# DAPlink_STM32F103-v1_0_0.net
KiCad netlist of a schematic drawn in EAGLE
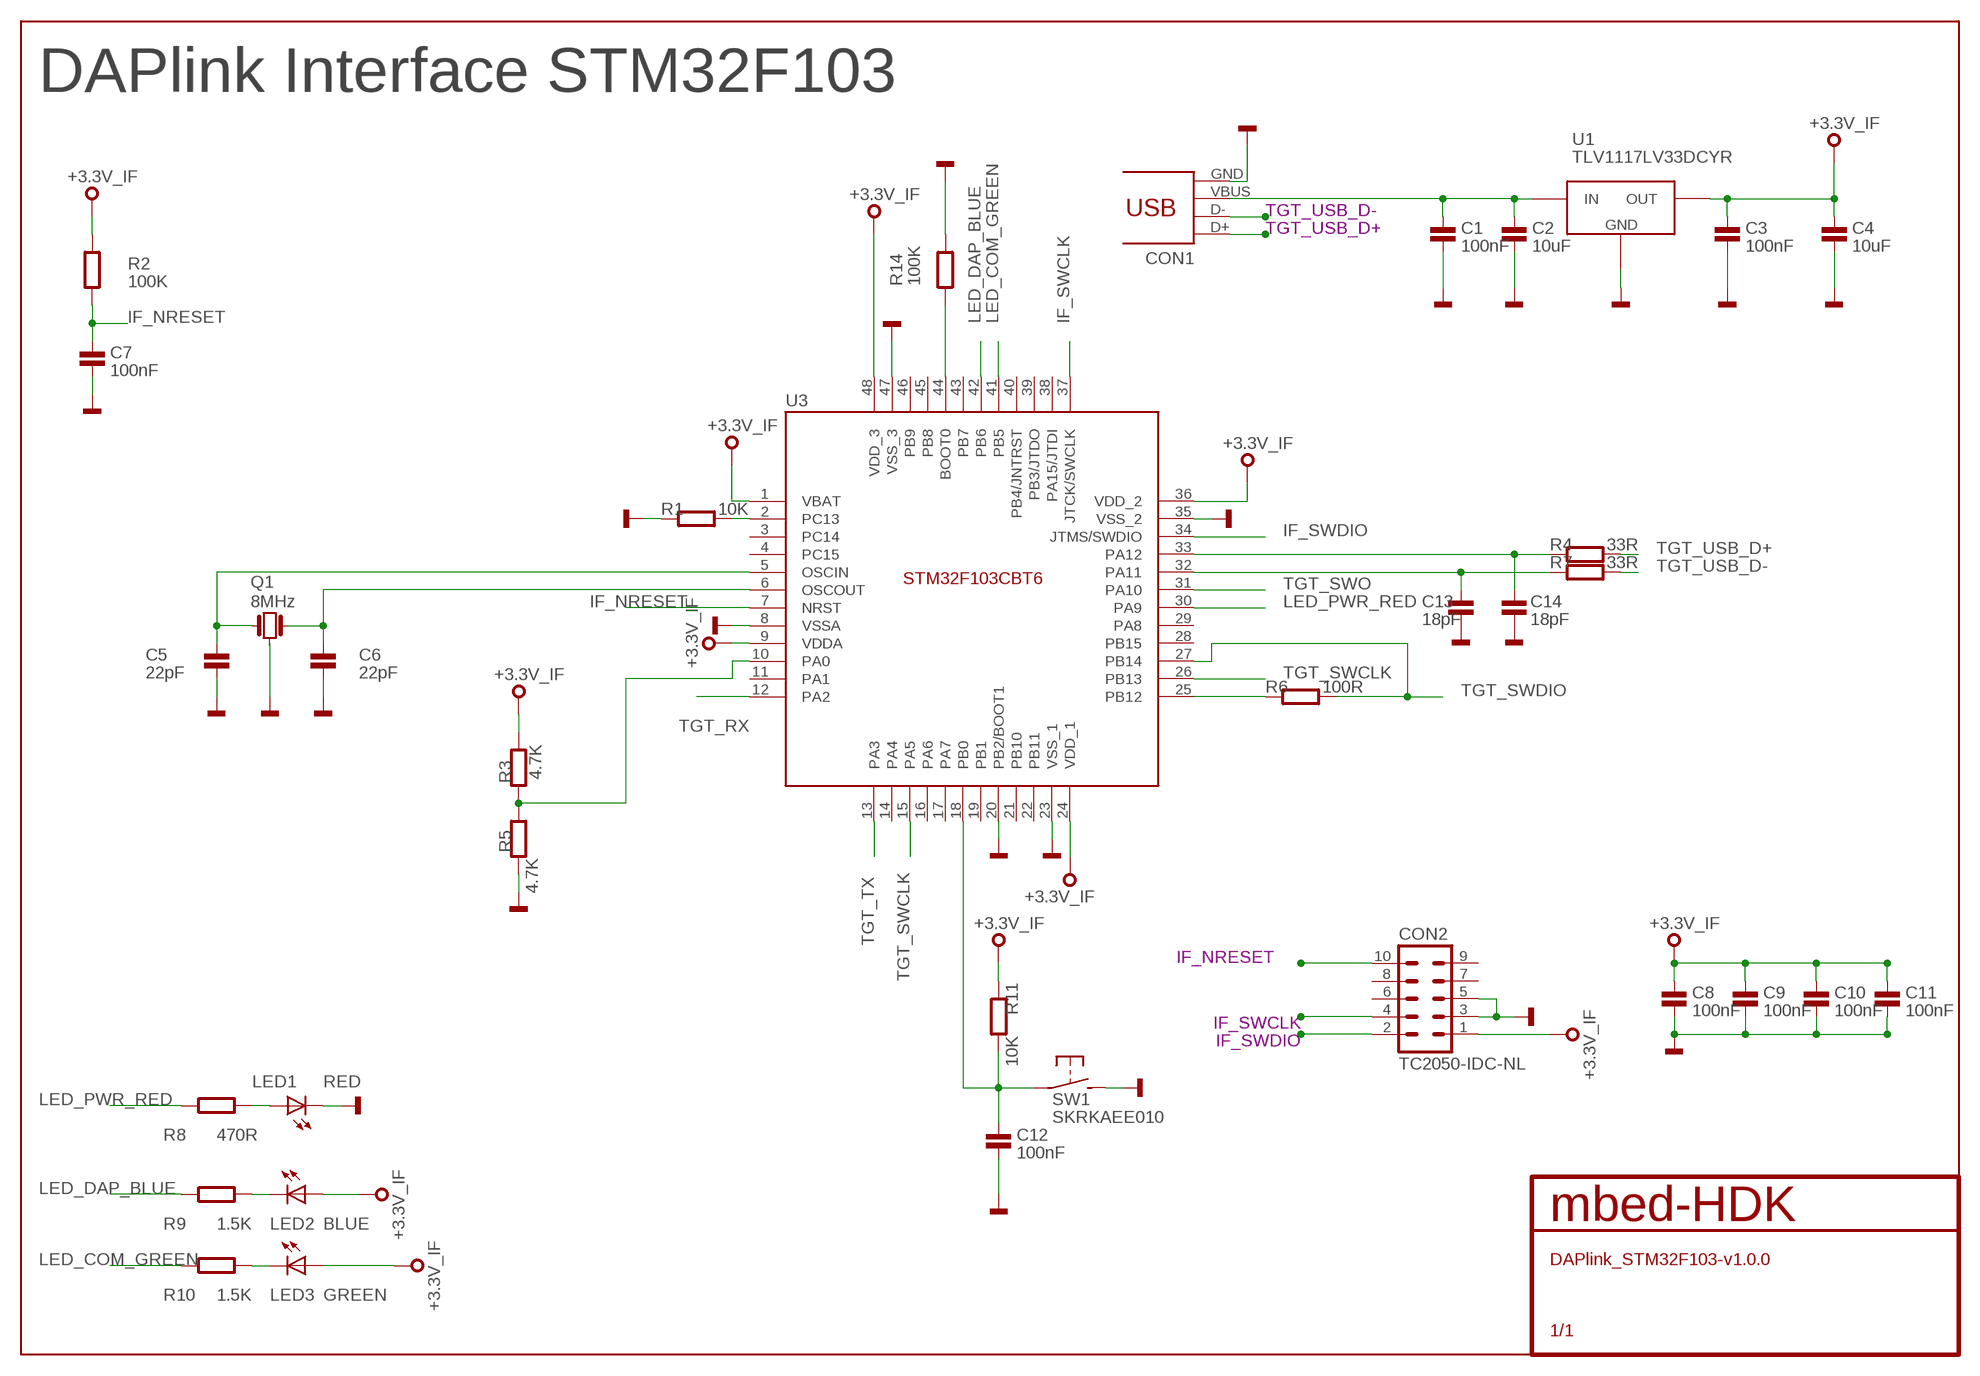
[diagram p0: schematic, sheet 1]

(export (version "E")
  (design (tool "Eeschema 10.0.6"))
  (components
    (comp (ref "C1")
      (value "100nF")
      (footprint "eagle-import:0402")
      (libsource (lib "eagle-import") (part "mbed-HDK-RLCQ_CAPACITOR0402"))
    )
    (comp (ref "C2")
      (value "10uF")
      (footprint "eagle-import:0603")
      (libsource (lib "eagle-import") (part "CAPACITOR0603"))
    )
    (comp (ref "C3")
      (value "100nF")
      (footprint "eagle-import:0402")
      (libsource (lib "eagle-import") (part "mbed-HDK-RLCQ_CAPACITOR0402"))
    )
    (comp (ref "C4")
      (value "10uF")
      (footprint "eagle-import:0603")
      (libsource (lib "eagle-import") (part "CAPACITOR0603"))
    )
    (comp (ref "C5")
      (value "22pF")
      (footprint "eagle-import:0402")
      (libsource (lib "eagle-import") (part "CAPACITOR0402"))
    )
    (comp (ref "C6")
      (value "22pF")
      (footprint "eagle-import:0402")
      (libsource (lib "eagle-import") (part "CAPACITOR0402"))
    )
    (comp (ref "C7")
      (value "100nF")
      (footprint "eagle-import:0402")
      (libsource (lib "eagle-import") (part "mbed-HDK-RLCQ_CAPACITOR0402"))
    )
    (comp (ref "C8")
      (value "100nF")
      (footprint "eagle-import:0402")
      (libsource (lib "eagle-import") (part "mbed-HDK-RLCQ_CAPACITOR0402"))
    )
    (comp (ref "C9")
      (value "100nF")
      (footprint "eagle-import:0402")
      (libsource (lib "eagle-import") (part "mbed-HDK-RLCQ_CAPACITOR0402"))
    )
    (comp (ref "C10")
      (value "100nF")
      (footprint "eagle-import:0402")
      (libsource (lib "eagle-import") (part "mbed-HDK-RLCQ_CAPACITOR0402"))
    )
    (comp (ref "C11")
      (value "100nF")
      (footprint "eagle-import:0402")
      (libsource (lib "eagle-import") (part "mbed-HDK-RLCQ_CAPACITOR0402"))
    )
    (comp (ref "C12")
      (value "100nF")
      (footprint "eagle-import:0402")
      (libsource (lib "eagle-import") (part "mbed-HDK-RLCQ_CAPACITOR0402"))
    )
    (comp (ref "C13")
      (value "18pF")
      (footprint "eagle-import:0402")
      (libsource (lib "eagle-import") (part "CAPACITOR0402"))
    )
    (comp (ref "C14")
      (value "18pF")
      (footprint "eagle-import:0402")
      (libsource (lib "eagle-import") (part "CAPACITOR0402"))
    )
    (comp (ref "CON1")
      (value "47346-0001")
      (footprint "eagle-import:USB-MICRO-B-H")
      (fields (field (name "MF") "MOLEX"))
      (libsource (lib "eagle-import") (part "47346-0001"))
    )
    (comp (ref "CON2")
      (value "TC2050-IDC-NL")
      (footprint "eagle-import:TC2050-IDC-NL")
      (libsource (lib "eagle-import") (part "TC2050-IDC-NL"))
    )
    (comp (ref "LED1")
      (value "RED")
      (footprint "eagle-import:CHIPLED_0603")
      (libsource (lib "eagle-import") (part "LED0603"))
    )
    (comp (ref "LED2")
      (value "BLUE")
      (footprint "eagle-import:CHIPLED_0603")
      (libsource (lib "eagle-import") (part "LED0603"))
    )
    (comp (ref "LED3")
      (value "GREEN")
      (footprint "eagle-import:CHIPLED_0603")
      (libsource (lib "eagle-import") (part "LED0603"))
    )
    (comp (ref "Q1")
      (value "8MHz")
      (footprint "eagle-import:CSTCE8M00G55-R0")
      (fields (field (name "MF") "Murata"))
      (libsource (lib "eagle-import") (part "CSTCE8M00G55-R0"))
    )
    (comp (ref "R1")
      (value "10K")
      (footprint "eagle-import:0402")
      (libsource (lib "eagle-import") (part "RESISTOR0402"))
    )
    (comp (ref "R2")
      (value "100K")
      (footprint "eagle-import:0402")
      (libsource (lib "eagle-import") (part "mbed-HDK-RLCQ_RESISTOR0402"))
    )
    (comp (ref "R3")
      (value "4.7K")
      (footprint "eagle-import:0402")
      (libsource (lib "eagle-import") (part "mbed-HDK-RLCQ_RESISTOR0402"))
    )
    (comp (ref "R4")
      (value "33R")
      (footprint "eagle-import:0402")
      (libsource (lib "eagle-import") (part "RESISTOR0402"))
    )
    (comp (ref "R5")
      (value "4.7K")
      (footprint "eagle-import:0402")
      (libsource (lib "eagle-import") (part "mbed-HDK-RLCQ_RESISTOR0402"))
    )
    (comp (ref "R6")
      (value "100R")
      (footprint "eagle-import:0402")
      (libsource (lib "eagle-import") (part "RESISTOR0402"))
    )
    (comp (ref "R7")
      (value "33R")
      (footprint "eagle-import:0402")
      (libsource (lib "eagle-import") (part "RESISTOR0402"))
    )
    (comp (ref "R8")
      (value "470R")
      (footprint "eagle-import:0402")
      (libsource (lib "eagle-import") (part "mbed-HDK-RLCQ_RESISTOR0402"))
    )
    (comp (ref "R9")
      (value "1.5K")
      (footprint "eagle-import:0402")
      (libsource (lib "eagle-import") (part "mbed-HDK-RLCQ_RESISTOR0402"))
    )
    (comp (ref "R10")
      (value "1.5K")
      (footprint "eagle-import:0402")
      (libsource (lib "eagle-import") (part "mbed-HDK-RLCQ_RESISTOR0402"))
    )
    (comp (ref "R11")
      (value "10K")
      (footprint "eagle-import:0402")
      (libsource (lib "eagle-import") (part "mbed-HDK-RLCQ_RESISTOR0402"))
    )
    (comp (ref "R14")
      (value "100K")
      (footprint "eagle-import:0402")
      (libsource (lib "eagle-import") (part "mbed-HDK-RLCQ_RESISTOR0402"))
    )
    (comp (ref "SW1")
      (value "SKRKAEE010")
      (footprint "eagle-import:SKRKAEE010")
      (fields (field (name "MF") "ALPS"))
      (libsource (lib "eagle-import") (part "SKRKAEE010"))
    )
    (comp (ref "U1")
      (value "TLV1117LV33DCYR")
      (footprint "eagle-import:SOT223")
      (fields (field (name "MF") "Texas Instruments"))
      (libsource (lib "eagle-import") (part "TLV1117LV33DCYR"))
    )
    (comp (ref "U3")
      (value "STM32F103CBT6")
      (footprint "eagle-import:LQFP48")
      (fields (field (name "MF") "STMicroelectronics"))
      (libsource (lib "eagle-import") (part "STM32F103CBT6"))
    )
  )
  (nets
    (net (code "1") (name "+3.3V_IF") (class "Default")
      (node (ref "C10") (pin "1") (pinfunction "P$1_1") (pintype "passive"))
      (node (ref "C11") (pin "1") (pinfunction "P$1_1") (pintype "passive"))
      (node (ref "C3") (pin "1") (pinfunction "P$1_1") (pintype "passive"))
      (node (ref "C4") (pin "1") (pinfunction "P$1_1") (pintype "passive"))
      (node (ref "C8") (pin "1") (pinfunction "P$1_1") (pintype "passive"))
      (node (ref "C9") (pin "1") (pinfunction "P$1_1") (pintype "passive"))
      (node (ref "CON2") (pin "1") (pinfunction "1_1") (pintype "passive"))
      (node (ref "LED2") (pin "A") (pinfunction "A_A") (pintype "passive"))
      (node (ref "LED3") (pin "A") (pinfunction "A_A") (pintype "passive"))
      (node (ref "R11") (pin "1") (pinfunction "P$1_1") (pintype "passive"))
      (node (ref "R2") (pin "1") (pinfunction "P$1_1") (pintype "passive"))
      (node (ref "R3") (pin "1") (pinfunction "P$1_1") (pintype "passive"))
      (node (ref "U1") (pin "2") (pinfunction "OUT_2") (pintype "bidirectional"))
      (node (ref "U1") (pin "4") (pinfunction "OUT_4") (pintype "bidirectional"))
      (node (ref "U3") (pin "1") (pinfunction "VBAT_1") (pintype "bidirectional"))
      (node (ref "U3") (pin "24") (pinfunction "VDD_1_24") (pintype "bidirectional"))
      (node (ref "U3") (pin "36") (pinfunction "VDD_2_36") (pintype "bidirectional"))
      (node (ref "U3") (pin "48") (pinfunction "VDD_3_48") (pintype "bidirectional"))
      (node (ref "U3") (pin "9") (pinfunction "VDDA_9") (pintype "bidirectional"))
    )
    (net (code "2") (name "/IF_NRESET") (class "Default")
      (node (ref "C7") (pin "1") (pinfunction "P$1_1") (pintype "passive"))
      (node (ref "CON2") (pin "10") (pinfunction "10_10") (pintype "passive"))
      (node (ref "R2") (pin "2") (pinfunction "P$2_2") (pintype "passive"))
      (node (ref "U3") (pin "7") (pinfunction "NRST_7") (pintype "bidirectional"))
    )
    (net (code "3") (name "/IF_SWCLK") (class "Default")
      (node (ref "CON2") (pin "4") (pinfunction "4_4") (pintype "passive"))
      (node (ref "U3") (pin "37") (pinfunction "JTCK/SWCLK_37") (pintype "bidirectional"))
    )
    (net (code "4") (name "/IF_SWDIO") (class "Default")
      (node (ref "CON2") (pin "2") (pinfunction "2_2") (pintype "passive"))
      (node (ref "U3") (pin "34") (pinfunction "JTMS/SWDIO_34") (pintype "bidirectional"))
    )
    (net (code "5") (name "/LED_COM_GREEN") (class "Default")
      (node (ref "R10") (pin "2") (pinfunction "P$2_2") (pintype "passive"))
      (node (ref "U3") (pin "41") (pinfunction "PB5_41") (pintype "bidirectional"))
    )
    (net (code "6") (name "/LED_DAP_BLUE") (class "Default")
      (node (ref "R9") (pin "2") (pinfunction "P$2_2") (pintype "passive"))
      (node (ref "U3") (pin "42") (pinfunction "PB6_42") (pintype "bidirectional"))
    )
    (net (code "7") (name "/LED_PWR_RED") (class "Default")
      (node (ref "R8") (pin "2") (pinfunction "P$2_2") (pintype "passive"))
      (node (ref "U3") (pin "30") (pinfunction "PA9_30") (pintype "bidirectional"))
    )
    (net (code "8") (name "/TGT_RX") (class "Default")
      (node (ref "U3") (pin "12") (pinfunction "PA2_12") (pintype "bidirectional"))
    )
    (net (code "9") (name "/TGT_SWCLK") (class "Default")
      (node (ref "U3") (pin "15") (pinfunction "PA5_15") (pintype "bidirectional"))
      (node (ref "U3") (pin "26") (pinfunction "PB13_26") (pintype "bidirectional"))
    )
    (net (code "10") (name "/TGT_SWDIO") (class "Default")
      (node (ref "R6") (pin "2") (pinfunction "P$2_2") (pintype "passive"))
      (node (ref "U3") (pin "27") (pinfunction "PB14_27") (pintype "bidirectional"))
    )
    (net (code "11") (name "/TGT_SWO") (class "Default")
      (node (ref "U3") (pin "31") (pinfunction "PA10_31") (pintype "bidirectional"))
    )
    (net (code "12") (name "/TGT_TX") (class "Default")
      (node (ref "U3") (pin "13") (pinfunction "PA3_13") (pintype "bidirectional"))
    )
    (net (code "13") (name "/TGT_USB_D+") (class "Default")
      (node (ref "CON1") (pin "D+") (pinfunction "D+_D+") (pintype "bidirectional"))
      (node (ref "R4") (pin "2") (pinfunction "P$2_2") (pintype "passive"))
    )
    (net (code "14") (name "/TGT_USB_D-") (class "Default")
      (node (ref "CON1") (pin "D-") (pinfunction "D-_D-") (pintype "bidirectional"))
      (node (ref "R7") (pin "2") (pinfunction "P$2_2") (pintype "passive"))
    )
    (net (code "15") (name "GND") (class "Default")
      (node (ref "C1") (pin "2") (pinfunction "P$2_2") (pintype "passive"))
      (node (ref "C10") (pin "2") (pinfunction "P$2_2") (pintype "passive"))
      (node (ref "C11") (pin "2") (pinfunction "P$2_2") (pintype "passive"))
      (node (ref "C12") (pin "2") (pinfunction "P$2_2") (pintype "passive"))
      (node (ref "C13") (pin "2") (pinfunction "P$2_2") (pintype "passive"))
      (node (ref "C14") (pin "2") (pinfunction "P$2_2") (pintype "passive"))
      (node (ref "C2") (pin "2") (pinfunction "P$2_2") (pintype "passive"))
      (node (ref "C3") (pin "2") (pinfunction "P$2_2") (pintype "passive"))
      (node (ref "C4") (pin "2") (pinfunction "P$2_2") (pintype "passive"))
      (node (ref "C5") (pin "2") (pinfunction "P$2_2") (pintype "passive"))
      (node (ref "C6") (pin "2") (pinfunction "P$2_2") (pintype "passive"))
      (node (ref "C7") (pin "2") (pinfunction "P$2_2") (pintype "passive"))
      (node (ref "C8") (pin "2") (pinfunction "P$2_2") (pintype "passive"))
      (node (ref "C9") (pin "2") (pinfunction "P$2_2") (pintype "passive"))
      (node (ref "CON1") (pin "GND") (pinfunction "GND_GND") (pintype "bidirectional"))
      (node (ref "CON2") (pin "3") (pinfunction "3_3") (pintype "passive"))
      (node (ref "CON2") (pin "5") (pinfunction "5_5") (pintype "passive"))
      (node (ref "LED1") (pin "C") (pinfunction "C_C") (pintype "passive"))
      (node (ref "Q1") (pin "2") (pinfunction "2_2") (pintype "passive"))
      (node (ref "R1") (pin "1") (pinfunction "P$1_1") (pintype "passive"))
      (node (ref "R14") (pin "1") (pinfunction "P$1_1") (pintype "passive"))
      (node (ref "R5") (pin "2") (pinfunction "P$2_2") (pintype "passive"))
      (node (ref "SW1") (pin "P$2") (pinfunction "S_P$2") (pintype "passive"))
      (node (ref "U1") (pin "1") (pinfunction "GND_1") (pintype "bidirectional"))
      (node (ref "U3") (pin "20") (pinfunction "PB2/BOOT1_20") (pintype "bidirectional"))
      (node (ref "U3") (pin "23") (pinfunction "VSS_1_23") (pintype "bidirectional"))
      (node (ref "U3") (pin "35") (pinfunction "VSS_2_35") (pintype "bidirectional"))
      (node (ref "U3") (pin "47") (pinfunction "VSS_3_47") (pintype "bidirectional"))
      (node (ref "U3") (pin "8") (pinfunction "VSSA_8") (pintype "bidirectional"))
    )
    (net (code "16") (name "Net-(C1-P$1)") (class "Default")
      (node (ref "C1") (pin "1") (pinfunction "P$1_1") (pintype "passive"))
      (node (ref "C2") (pin "1") (pinfunction "P$1_1") (pintype "passive"))
      (node (ref "CON1") (pin "VBUS") (pinfunction "VBUS_VBUS") (pintype "bidirectional"))
      (node (ref "U1") (pin "3") (pinfunction "IN_3") (pintype "bidirectional"))
    )
    (net (code "17") (name "Net-(C5-P$1)") (class "Default")
      (node (ref "C5") (pin "1") (pinfunction "P$1_1") (pintype "passive"))
      (node (ref "Q1") (pin "1") (pinfunction "1_1") (pintype "passive"))
      (node (ref "U3") (pin "5") (pinfunction "OSCIN_5") (pintype "bidirectional"))
    )
    (net (code "18") (name "Net-(C6-P$1)") (class "Default")
      (node (ref "C6") (pin "1") (pinfunction "P$1_1") (pintype "passive"))
      (node (ref "Q1") (pin "3") (pinfunction "3_3") (pintype "passive"))
      (node (ref "U3") (pin "6") (pinfunction "OSCOUT_6") (pintype "bidirectional"))
    )
    (net (code "19") (name "Net-(C12-P$1)") (class "Default")
      (node (ref "C12") (pin "1") (pinfunction "P$1_1") (pintype "passive"))
      (node (ref "R11") (pin "2") (pinfunction "P$2_2") (pintype "passive"))
      (node (ref "SW1") (pin "P$1") (pinfunction "P_P$1") (pintype "passive"))
      (node (ref "U3") (pin "18") (pinfunction "PB0_18") (pintype "bidirectional"))
    )
    (net (code "20") (name "Net-(C13-P$1)") (class "Default")
      (node (ref "C13") (pin "1") (pinfunction "P$1_1") (pintype "passive"))
      (node (ref "R7") (pin "1") (pinfunction "P$1_1") (pintype "passive"))
      (node (ref "U3") (pin "32") (pinfunction "PA11_32") (pintype "bidirectional"))
    )
    (net (code "21") (name "Net-(C14-P$1)") (class "Default")
      (node (ref "C14") (pin "1") (pinfunction "P$1_1") (pintype "passive"))
      (node (ref "R4") (pin "1") (pinfunction "P$1_1") (pintype "passive"))
      (node (ref "U3") (pin "33") (pinfunction "PA12_33") (pintype "bidirectional"))
    )
    (net (code "22") (name "Net-(R1-P$2)") (class "Default")
      (node (ref "R1") (pin "2") (pinfunction "P$2_2") (pintype "passive"))
      (node (ref "U3") (pin "2") (pinfunction "PC13_2") (pintype "bidirectional"))
    )
    (net (code "23") (name "Net-(R3-P$2)") (class "Default")
      (node (ref "R3") (pin "2") (pinfunction "P$2_2") (pintype "passive"))
      (node (ref "R5") (pin "1") (pinfunction "P$1_1") (pintype "passive"))
      (node (ref "U3") (pin "10") (pinfunction "PA0_10") (pintype "bidirectional"))
    )
    (net (code "24") (name "Net-(R6-P$1)") (class "Default")
      (node (ref "R6") (pin "1") (pinfunction "P$1_1") (pintype "passive"))
      (node (ref "U3") (pin "25") (pinfunction "PB12_25") (pintype "bidirectional"))
    )
    (net (code "25") (name "Net-(R8-P$1)") (class "Default")
      (node (ref "LED1") (pin "A") (pinfunction "A_A") (pintype "passive"))
      (node (ref "R8") (pin "1") (pinfunction "P$1_1") (pintype "passive"))
    )
    (net (code "26") (name "Net-(R9-P$1)") (class "Default")
      (node (ref "LED2") (pin "C") (pinfunction "C_C") (pintype "passive"))
      (node (ref "R9") (pin "1") (pinfunction "P$1_1") (pintype "passive"))
    )
    (net (code "27") (name "Net-(R10-P$1)") (class "Default")
      (node (ref "LED3") (pin "C") (pinfunction "C_C") (pintype "passive"))
      (node (ref "R10") (pin "1") (pinfunction "P$1_1") (pintype "passive"))
    )
    (net (code "28") (name "Net-(R14-P$2)") (class "Default")
      (node (ref "R14") (pin "2") (pinfunction "P$2_2") (pintype "passive"))
      (node (ref "U3") (pin "44") (pinfunction "BOOT0_44") (pintype "bidirectional"))
    )
    (net (code "29") (name "unconnected-(CON2-Pad6)") (class "Default")
      (node (ref "CON2") (pin "6") (pinfunction "6_6") (pintype "passive"))
    )
    (net (code "30") (name "unconnected-(CON2-Pad7)") (class "Default")
      (node (ref "CON2") (pin "7") (pinfunction "7_7") (pintype "passive"))
    )
    (net (code "31") (name "unconnected-(CON2-Pad8)") (class "Default")
      (node (ref "CON2") (pin "8") (pinfunction "8_8") (pintype "passive"))
    )
    (net (code "32") (name "unconnected-(CON2-Pad9)") (class "Default")
      (node (ref "CON2") (pin "9") (pinfunction "9_9") (pintype "passive"))
    )
    (net (code "33") (name "unconnected-(U3-PA1-Pad11)") (class "Default")
      (node (ref "U3") (pin "11") (pinfunction "PA1_11") (pintype "bidirectional"))
    )
    (net (code "34") (name "unconnected-(U3-PA4-Pad14)") (class "Default")
      (node (ref "U3") (pin "14") (pinfunction "PA4_14") (pintype "bidirectional"))
    )
    (net (code "35") (name "unconnected-(U3-PA6-Pad16)") (class "Default")
      (node (ref "U3") (pin "16") (pinfunction "PA6_16") (pintype "bidirectional"))
    )
    (net (code "36") (name "unconnected-(U3-PA7-Pad17)") (class "Default")
      (node (ref "U3") (pin "17") (pinfunction "PA7_17") (pintype "bidirectional"))
    )
    (net (code "37") (name "unconnected-(U3-PA8-Pad29)") (class "Default")
      (node (ref "U3") (pin "29") (pinfunction "PA8_29") (pintype "bidirectional"))
    )
    (net (code "38") (name "unconnected-(U3-PA15{slash}JTDI-Pad38)") (class "Default")
      (node (ref "U3") (pin "38") (pinfunction "PA15/JTDI_38") (pintype "bidirectional"))
    )
    (net (code "39") (name "unconnected-(U3-PB1-Pad19)") (class "Default")
      (node (ref "U3") (pin "19") (pinfunction "PB1_19") (pintype "bidirectional"))
    )
    (net (code "40") (name "unconnected-(U3-PB3{slash}JTDO-Pad39)") (class "Default")
      (node (ref "U3") (pin "39") (pinfunction "PB3/JTDO_39") (pintype "bidirectional"))
    )
    (net (code "41") (name "unconnected-(U3-PB4{slash}JNTRST-Pad40)") (class "Default")
      (node (ref "U3") (pin "40") (pinfunction "PB4/JNTRST_40") (pintype "bidirectional"))
    )
    (net (code "42") (name "unconnected-(U3-PB7-Pad43)") (class "Default")
      (node (ref "U3") (pin "43") (pinfunction "PB7_43") (pintype "bidirectional"))
    )
    (net (code "43") (name "unconnected-(U3-PB8-Pad45)") (class "Default")
      (node (ref "U3") (pin "45") (pinfunction "PB8_45") (pintype "bidirectional"))
    )
    (net (code "44") (name "unconnected-(U3-PB9-Pad46)") (class "Default")
      (node (ref "U3") (pin "46") (pinfunction "PB9_46") (pintype "bidirectional"))
    )
    (net (code "45") (name "unconnected-(U3-PB10-Pad21)") (class "Default")
      (node (ref "U3") (pin "21") (pinfunction "PB10_21") (pintype "bidirectional"))
    )
    (net (code "46") (name "unconnected-(U3-PB11-Pad22)") (class "Default")
      (node (ref "U3") (pin "22") (pinfunction "PB11_22") (pintype "bidirectional"))
    )
    (net (code "47") (name "unconnected-(U3-PB15-Pad28)") (class "Default")
      (node (ref "U3") (pin "28") (pinfunction "PB15_28") (pintype "bidirectional"))
    )
    (net (code "48") (name "unconnected-(U3-PC14-Pad3)") (class "Default")
      (node (ref "U3") (pin "3") (pinfunction "PC14_3") (pintype "bidirectional"))
    )
    (net (code "49") (name "unconnected-(U3-PC15-Pad4)") (class "Default")
      (node (ref "U3") (pin "4") (pinfunction "PC15_4") (pintype "bidirectional"))
    )
  )
)
